# bg_sensor.net
KiCad netlist of a schematic drawn in Altium Designer
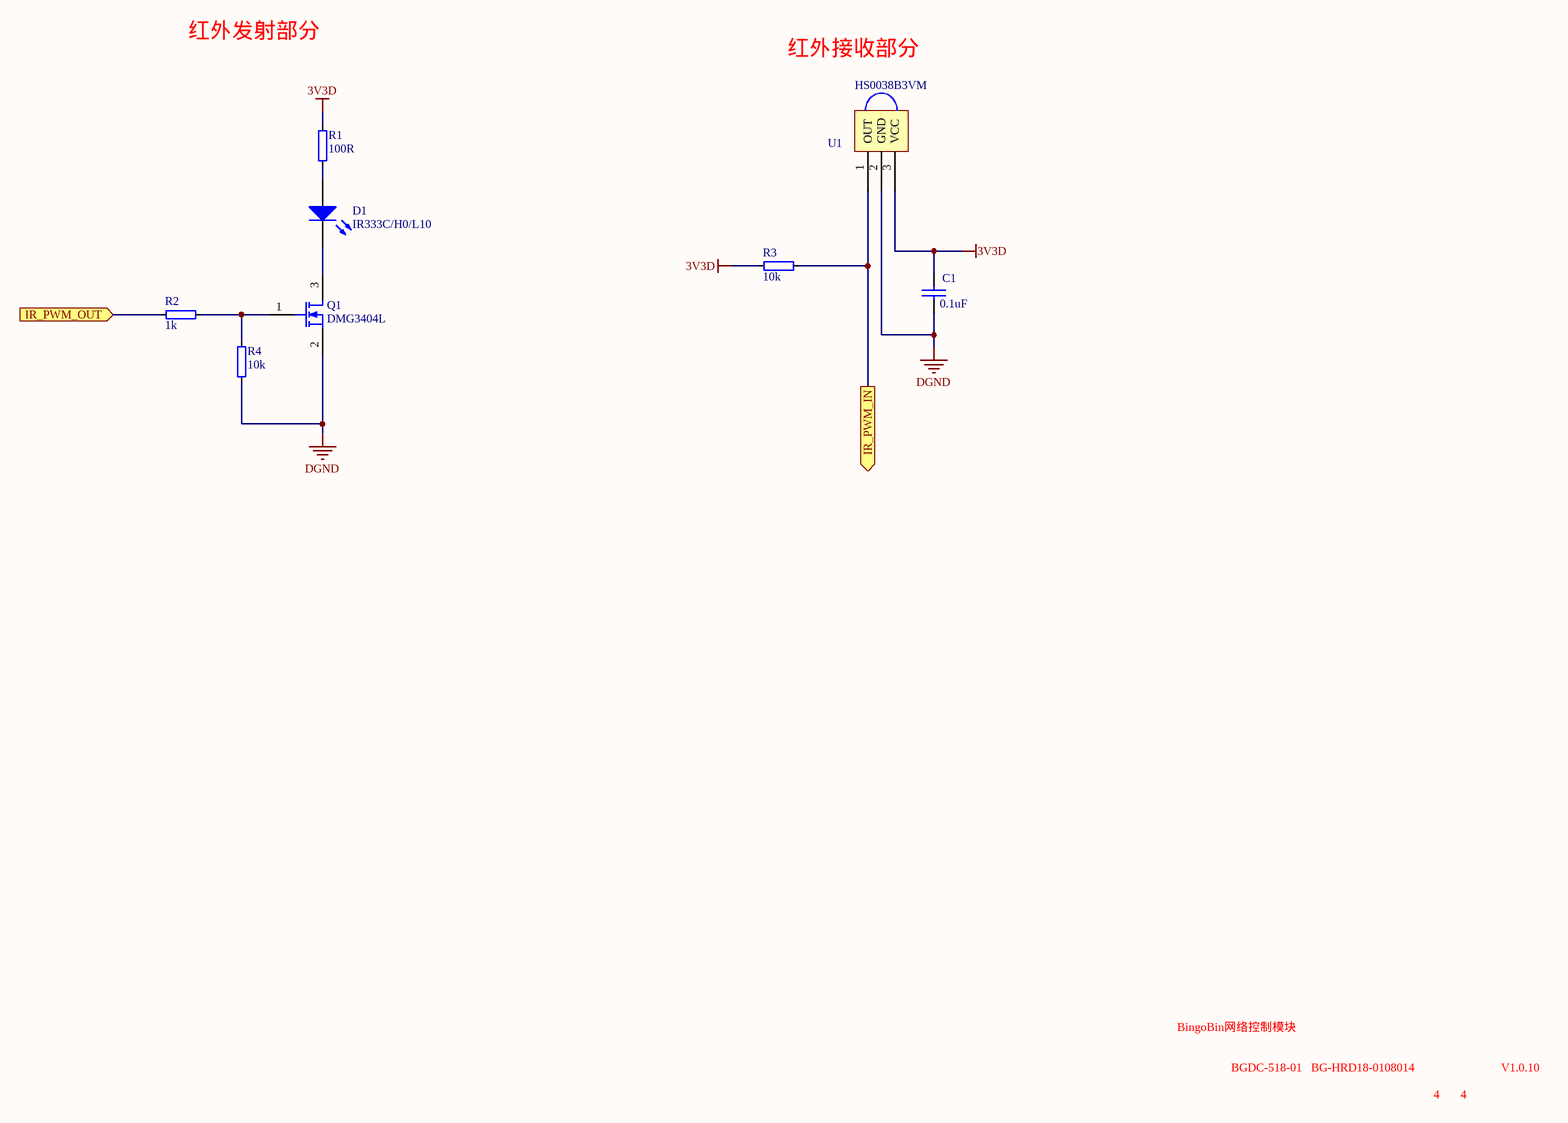
[diagram p0: bg_sensor.SchDoc]

(export (version "E")
  (design (tool "Eeschema 10.0.6"))
  (components
    (comp (ref "C1")
      (value "0.1uF")
      (footprint "C0603")
      (description "Capacitor, Ceramic, 0.1uF, 16V, 10%, 0603, X7R")
      (fields (field (name "MANUFACTURER") "muRata"))
      (libsource (lib "bg_sch") (part "C0603"))
    )
    (comp (ref "D1")
      (value "IR333C/H0/L10")
      (footprint "LED")
      (description "Typical RED GaAs LED")
      (fields (field (name "MANUFACTURER") "EVERLIGHT"))
      (libsource (lib "Miscellaneous Devices") (part "LED1"))
    )
    (comp (ref "Q1")
      (value "DMG3404L")
      (footprint "sot-23")
      (description "N沟道,30V,5.6A,27mΩ(Typ,@Vgs=4.5V)")
      (fields (field (name "MANUFACTURER") "DIODES") (field (name "PUBLISHER") "Altium Limited"))
      (libsource (lib "Miscellaneous Devices") (part "MOSFET-N"))
    )
    (comp (ref "R1")
      (value "100R")
      (footprint "R0603")
      (description "RES, THICK FILM, 10K, 5%, 1/10W, 0603")
      (fields
        (field (name "PART NUMBER") "R0402-10k")
        (field (name "MANUFACTURER") "muRata")
        (field (name "PUBLISHER") "Nordic Semiconductor")
      )
      (libsource (lib "Nordic Passive DB") (part "RES_1"))
    )
    (comp (ref "R2")
      (value "1k")
      (footprint "R0603")
      (description "RES, THICK FILM, 10K, 5%, 1/10W, 0603")
      (fields
        (field (name "PART NUMBER") "R0402-10k")
        (field (name "MANUFACTURER") "muRata")
        (field (name "PUBLISHER") "Nordic Semiconductor")
      )
      (libsource (lib "Nordic Passive DB") (part "RES_1"))
    )
    (comp (ref "R3")
      (value "10k")
      (footprint "R0603")
      (description "RES, THICK FILM, 10K, 5%, 1/10W, 0603")
      (fields
        (field (name "PART NUMBER") "R0402-10k")
        (field (name "MANUFACTURER") "muRata")
        (field (name "PUBLISHER") "Nordic Semiconductor")
      )
      (libsource (lib "Nordic Passive DB") (part "RES_1"))
    )
    (comp (ref "R4")
      (value "10k")
      (footprint "R0603")
      (description "RES, THICK FILM, 10K, 5%, 1/10W, 0603")
      (fields
        (field (name "PART NUMBER") "R0402-10k")
        (field (name "MANUFACTURER") "muRata")
        (field (name "PUBLISHER") "Nordic Semiconductor")
      )
      (libsource (lib "Nordic Passive DB") (part "RES_1"))
    )
    (comp (ref "U1")
      (value "HS0038B3VM")
      (footprint "DIP_3")
      (fields (field (name "MANUFACTURER") "Vishay"))
      (libsource (lib "Schlib1") (part "1838"))
    )
  )
  (nets
    (net (code "1") (name "/IR_PWM_IN") (class "Default")
      (node (ref "R3") (pin "1") (pinfunction "1_1") (pintype "passive"))
      (node (ref "U1") (pin "1") (pinfunction "OUT_1") (pintype "passive"))
    )
    (net (code "2") (name "/IR_PWM_OUT") (class "Default")
      (node (ref "R2") (pin "1") (pinfunction "1_1") (pintype "passive"))
    )
    (net (code "3") (name "3V3D") (class "Default")
      (node (ref "C1") (pin "2") (pinfunction "2_2") (pintype "passive"))
      (node (ref "R1") (pin "2") (pinfunction "2_2") (pintype "passive"))
      (node (ref "R3") (pin "2") (pinfunction "2_2") (pintype "passive"))
      (node (ref "U1") (pin "3") (pinfunction "VCC_3") (pintype "passive"))
    )
    (net (code "4") (name "DGND") (class "Default")
      (node (ref "C1") (pin "1") (pinfunction "1_1") (pintype "passive"))
      (node (ref "Q1") (pin "2") (pinfunction "S_2") (pintype "passive"))
      (node (ref "R4") (pin "1") (pinfunction "1_1") (pintype "passive"))
      (node (ref "U1") (pin "2") (pinfunction "GND_2") (pintype "passive"))
    )
    (net (code "5") (name "Net-(D1-A)") (class "Default")
      (node (ref "D1") (pin "1") (pinfunction "A_1") (pintype "passive"))
      (node (ref "R1") (pin "1") (pinfunction "1_1") (pintype "passive"))
    )
    (net (code "6") (name "Net-(D1-K)") (class "Default")
      (node (ref "D1") (pin "2") (pinfunction "K_2") (pintype "passive"))
      (node (ref "Q1") (pin "3") (pinfunction "D_3") (pintype "passive"))
    )
    (net (code "7") (name "Net-(Q1-G)") (class "Default")
      (node (ref "Q1") (pin "1") (pinfunction "G_1") (pintype "passive"))
      (node (ref "R2") (pin "2") (pinfunction "2_2") (pintype "passive"))
      (node (ref "R4") (pin "2") (pinfunction "2_2") (pintype "passive"))
    )
  )
)
